# grayhill-knob-board.net
KiCad netlist of a schematic drawn in EAGLE
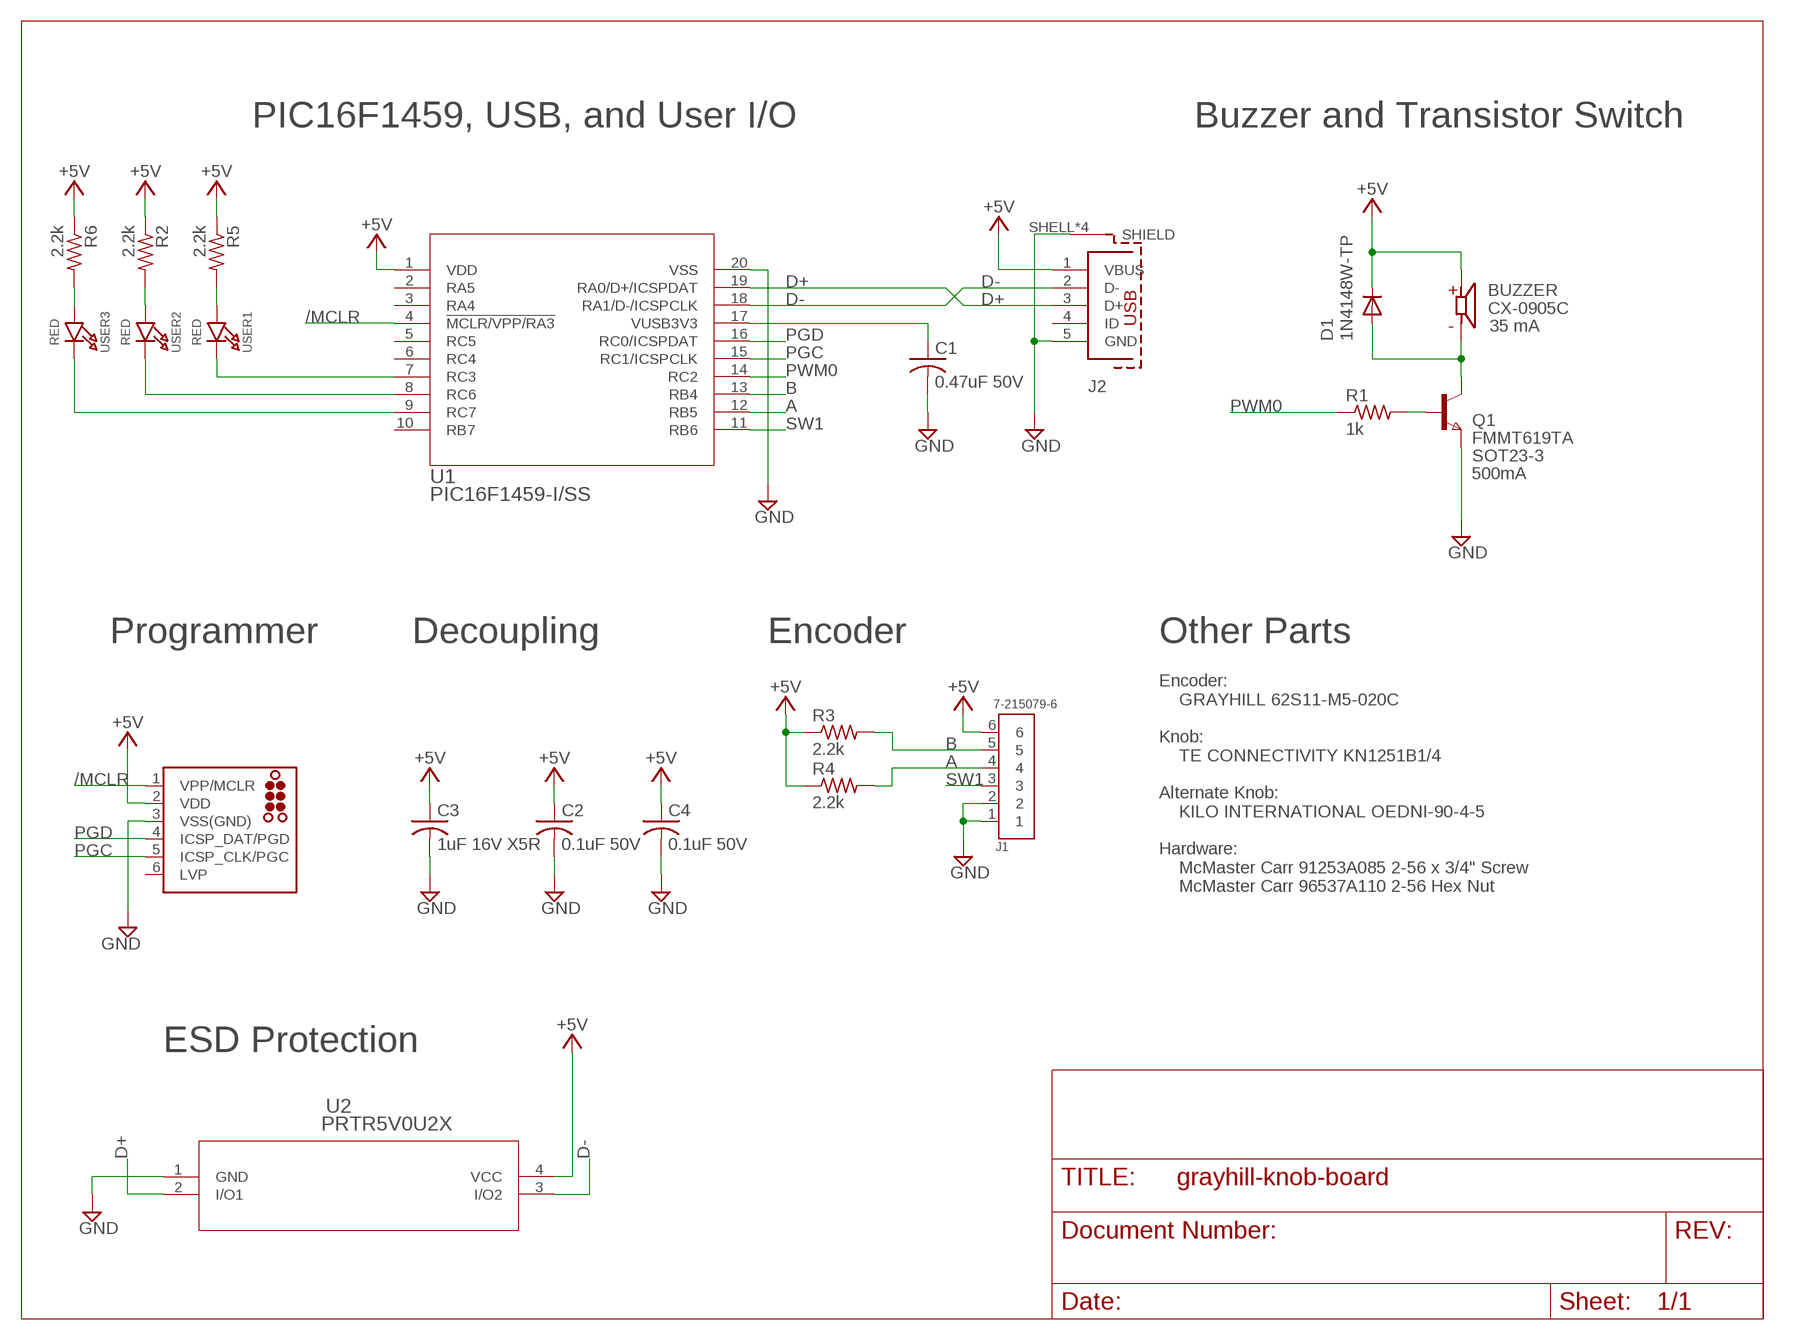
[diagram p0: schematic, sheet 1]

(export (version "E")
  (design (tool "Eeschema 10.0.6"))
  (components
    (comp (ref "BUZZER")
      (value "CX-0905C")
      (footprint "eagle-import:CUI_CX-0905C")
      (fields (field (name "MF") "CUI"))
      (libsource (lib "eagle-import") (part "CX-0905C"))
    )
    (comp (ref "C1")
      (value "0.47uF 50V")
      (footprint "eagle-import:C1206K")
      (fields (field (name "MFR") "KEMET") (field (name "MFR_PART_NO") "C1206C474K5RACTU"))
      (libsource (lib "eagle-import") (part "C-USC1206K"))
    )
    (comp (ref "C2")
      (value "0.1uF 50V")
      (footprint "eagle-import:C1206K")
      (fields (field (name "MFR") "KEMET") (field (name "MFR_PART_NO") "C1206S104M5RACTU"))
      (libsource (lib "eagle-import") (part "C-USC1206K"))
    )
    (comp (ref "C3")
      (value "1uF 16V X5R")
      (footprint "eagle-import:C1210")
      (fields (field (name "MFR") "KEMET") (field (name "MFR_PART_NO") "C1210C105K4PACTU"))
      (libsource (lib "eagle-import") (part "C-USC1210"))
    )
    (comp (ref "C4")
      (value "0.1uF 50V")
      (footprint "eagle-import:C1206K")
      (fields (field (name "MFR") "KEMET") (field (name "MFR_PART_NO") "C1206S104M5RACTU"))
      (libsource (lib "eagle-import") (part "C-USC1206K"))
    )
    (comp (ref "D1")
      (value "1N4148W-TP")
      (footprint "eagle-import:SOD123")
      (libsource (lib "eagle-import") (part "DIODE-SOD123"))
    )
    (comp (ref "J1")
      (value "7-215079-6")
      (footprint "eagle-import:TE_7-215079-6")
      (fields (field (name "DIGI-KEY_PART_NUMBER") "A30729CT-ND") (field (name "MF") "TE Connectivity"))
      (libsource (lib "eagle-import") (part "7-215079-6"))
    )
    (comp (ref "J2")
      (value "629105136821")
      (footprint "eagle-import:629105136821")
      (libsource (lib "eagle-import") (part "629105136821"))
    )
    (comp (ref "J3")
      (value "TC2030-MCP-NL")
      (footprint "eagle-import:TC2030-MCP-NL")
      (libsource (lib "eagle-import") (part "TC2030-MCP-NL"))
    )
    (comp (ref "Q1")
      (value "FMMT619TA")
      (footprint "eagle-import:SOT-23")
      (fields (field (name "MPN") "DSS20201L-7"))
      (libsource (lib "eagle-import") (part "NPNSOT23"))
    )
    (comp (ref "R1")
      (value "1k")
      (footprint "eagle-import:R0805")
      (libsource (lib "eagle-import") (part "R-US_R0805"))
    )
    (comp (ref "R2")
      (value "2.2k")
      (footprint "eagle-import:R0805")
      (libsource (lib "eagle-import") (part "R-US_R0805"))
    )
    (comp (ref "R3")
      (value "2.2k")
      (footprint "eagle-import:R0805")
      (libsource (lib "eagle-import") (part "R-US_R0805"))
    )
    (comp (ref "R4")
      (value "2.2k")
      (footprint "eagle-import:R0805")
      (libsource (lib "eagle-import") (part "R-US_R0805"))
    )
    (comp (ref "R5")
      (value "2.2k")
      (footprint "eagle-import:R0805")
      (libsource (lib "eagle-import") (part "R-US_R0805"))
    )
    (comp (ref "R6")
      (value "2.2k")
      (footprint "eagle-import:R0805")
      (libsource (lib "eagle-import") (part "R-US_R0805"))
    )
    (comp (ref "U1")
      (value "PIC16F1459-I/SS")
      (footprint "eagle-import:SSOP20_MC")
      (fields (field (name "MANUFACTURER_PART_NUMBER") "PIC16F1459ISS"))
      (libsource (lib "eagle-import") (part "PIC16F1459-I/SS"))
    )
    (comp (ref "U2")
      (value "PRTR5V0U2X")
      (footprint "eagle-import:SOT143B")
      (libsource (lib "eagle-import") (part "PRTR5V0U2X"))
    )
    (comp (ref "USER1")
      (value "RED")
      (footprint "eagle-import:CHIPLED_0805_NOOUTLINE")
      (libsource (lib "eagle-import") (part "LED0805_NOOUTLINE"))
    )
    (comp (ref "USER2")
      (value "RED")
      (footprint "eagle-import:CHIPLED_0805_NOOUTLINE")
      (libsource (lib "eagle-import") (part "LED0805_NOOUTLINE"))
    )
    (comp (ref "USER3")
      (value "RED")
      (footprint "eagle-import:CHIPLED_0805_NOOUTLINE")
      (libsource (lib "eagle-import") (part "LED0805_NOOUTLINE"))
    )
  )
  (nets
    (net (code "1") (name "+5V") (class "Default")
      (node (ref "BUZZER") (pin "P") (pinfunction "P_P") (pintype "passive"))
      (node (ref "C2") (pin "1") (pinfunction "1_1") (pintype "passive"))
      (node (ref "C3") (pin "1") (pinfunction "1_1") (pintype "passive"))
      (node (ref "C4") (pin "1") (pinfunction "1_1") (pintype "passive"))
      (node (ref "D1") (pin "C") (pinfunction "C_C") (pintype "passive"))
      (node (ref "J1") (pin "6") (pinfunction "6_6") (pintype "passive"))
      (node (ref "J2") (pin "1") (pinfunction "VBUS_1") (pintype "passive"))
      (node (ref "J3") (pin "2") (pinfunction "VDD_2") (pintype "power_in"))
      (node (ref "R2") (pin "1") (pinfunction "1_1") (pintype "passive"))
      (node (ref "R3") (pin "1") (pinfunction "1_1") (pintype "passive"))
      (node (ref "R4") (pin "1") (pinfunction "1_1") (pintype "passive"))
      (node (ref "R5") (pin "1") (pinfunction "1_1") (pintype "passive"))
      (node (ref "R6") (pin "1") (pinfunction "1_1") (pintype "passive"))
      (node (ref "U1") (pin "1") (pinfunction "VDD_1") (pintype "power_in"))
      (node (ref "U2") (pin "4") (pinfunction "VCC_4") (pintype "passive"))
    )
    (net (code "2") (name "/A") (class "Default")
      (node (ref "J1") (pin "4") (pinfunction "4_4") (pintype "passive"))
      (node (ref "R4") (pin "2") (pinfunction "2_2") (pintype "passive"))
      (node (ref "U1") (pin "12") (pinfunction "RB5_12") (pintype "bidirectional"))
    )
    (net (code "3") (name "/B") (class "Default")
      (node (ref "J1") (pin "5") (pinfunction "5_5") (pintype "passive"))
      (node (ref "R3") (pin "2") (pinfunction "2_2") (pintype "passive"))
      (node (ref "U1") (pin "13") (pinfunction "RB4_13") (pintype "bidirectional"))
    )
    (net (code "4") (name "/D+") (class "Default")
      (node (ref "J2") (pin "3") (pinfunction "D+_3") (pintype "passive"))
      (node (ref "U1") (pin "19") (pinfunction "RA0/D+/ICSPDAT_19") (pintype "bidirectional"))
      (node (ref "U2") (pin "2") (pinfunction "I/O1_2") (pintype "passive"))
    )
    (net (code "5") (name "/D-") (class "Default")
      (node (ref "J2") (pin "2") (pinfunction "D-_2") (pintype "passive"))
      (node (ref "U1") (pin "18") (pinfunction "RA1/D-/ICSPCLK_18") (pintype "bidirectional"))
      (node (ref "U2") (pin "3") (pinfunction "I/O2_3") (pintype "passive"))
    )
    (net (code "6") (name "/PGC") (class "Default")
      (node (ref "J3") (pin "5") (pinfunction "ICSP_CLK/PGC_5") (pintype "output"))
      (node (ref "U1") (pin "15") (pinfunction "RC1/ICSPCLK_15") (pintype "bidirectional"))
    )
    (net (code "7") (name "/PGD") (class "Default")
      (node (ref "J3") (pin "4") (pinfunction "ICSP_DAT/PGD_4") (pintype "bidirectional"))
      (node (ref "U1") (pin "16") (pinfunction "RC0/ICSPDAT_16") (pintype "bidirectional"))
    )
    (net (code "8") (name "/PWM0") (class "Default")
      (node (ref "R1") (pin "1") (pinfunction "1_1") (pintype "passive"))
      (node (ref "U1") (pin "14") (pinfunction "RC2_14") (pintype "bidirectional"))
    )
    (net (code "9") (name "/SW1") (class "Default")
      (node (ref "J1") (pin "3") (pinfunction "3_3") (pintype "passive"))
      (node (ref "U1") (pin "11") (pinfunction "RB6_11") (pintype "bidirectional"))
    )
    (net (code "10") (name "/{slash}MCLR") (class "Default")
      (node (ref "J3") (pin "1") (pinfunction "VPP/MCLR_1") (pintype "passive"))
      (node (ref "U1") (pin "4") (pinfunction "~{MCLR/VPP/RA3}_4") (pintype "bidirectional"))
    )
    (net (code "11") (name "GND") (class "Default")
      (node (ref "C1") (pin "2") (pinfunction "2_2") (pintype "passive"))
      (node (ref "C2") (pin "2") (pinfunction "2_2") (pintype "passive"))
      (node (ref "C3") (pin "2") (pinfunction "2_2") (pintype "passive"))
      (node (ref "C4") (pin "2") (pinfunction "2_2") (pintype "passive"))
      (node (ref "J1") (pin "1") (pinfunction "1_1") (pintype "passive"))
      (node (ref "J1") (pin "2") (pinfunction "2_2") (pintype "passive"))
      (node (ref "J2") (pin "5") (pinfunction "GND_5") (pintype "passive"))
      (node (ref "J2") (pin "SHELL") (pinfunction "SHIELD_SHELL") (pintype "passive"))
      (node (ref "J2") (pin "SHELL1") (pinfunction "SHIELD_SHELL1") (pintype "passive"))
      (node (ref "J2") (pin "SHELL2") (pinfunction "SHIELD_SHELL2") (pintype "passive"))
      (node (ref "J2") (pin "SHELL3") (pinfunction "SHIELD_SHELL3") (pintype "passive"))
      (node (ref "J3") (pin "3") (pinfunction "VSS(GND)_3") (pintype "power_in"))
      (node (ref "Q1") (pin "2") (pinfunction "E_2") (pintype "passive"))
      (node (ref "U1") (pin "20") (pinfunction "VSS_20") (pintype "power_in"))
      (node (ref "U2") (pin "1") (pinfunction "GND_1") (pintype "passive"))
    )
    (net (code "12") (name "Net-(Q1-B)") (class "Default")
      (node (ref "Q1") (pin "3") (pinfunction "B_3") (pintype "passive"))
      (node (ref "R1") (pin "2") (pinfunction "2_2") (pintype "passive"))
    )
    (net (code "13") (name "Net-(Q1-C)") (class "Default")
      (node (ref "BUZZER") (pin "N") (pinfunction "N_N") (pintype "passive"))
      (node (ref "D1") (pin "A") (pinfunction "A_A") (pintype "passive"))
      (node (ref "Q1") (pin "1") (pinfunction "C_1") (pintype "passive"))
    )
    (net (code "14") (name "Net-(R2-Pad2)") (class "Default")
      (node (ref "R2") (pin "2") (pinfunction "2_2") (pintype "passive"))
      (node (ref "USER2") (pin "A") (pinfunction "A_A") (pintype "passive"))
    )
    (net (code "15") (name "Net-(R5-Pad2)") (class "Default")
      (node (ref "R5") (pin "2") (pinfunction "2_2") (pintype "passive"))
      (node (ref "USER1") (pin "A") (pinfunction "A_A") (pintype "passive"))
    )
    (net (code "16") (name "Net-(R6-Pad2)") (class "Default")
      (node (ref "R6") (pin "2") (pinfunction "2_2") (pintype "passive"))
      (node (ref "USER3") (pin "A") (pinfunction "A_A") (pintype "passive"))
    )
    (net (code "17") (name "Net-(U1-RC3)") (class "Default")
      (node (ref "U1") (pin "7") (pinfunction "RC3_7") (pintype "bidirectional"))
      (node (ref "USER1") (pin "C") (pinfunction "C_C") (pintype "passive"))
    )
    (net (code "18") (name "Net-(U1-RC6)") (class "Default")
      (node (ref "U1") (pin "8") (pinfunction "RC6_8") (pintype "bidirectional"))
      (node (ref "USER2") (pin "C") (pinfunction "C_C") (pintype "passive"))
    )
    (net (code "19") (name "Net-(U1-RC7)") (class "Default")
      (node (ref "U1") (pin "9") (pinfunction "RC7_9") (pintype "bidirectional"))
      (node (ref "USER3") (pin "C") (pinfunction "C_C") (pintype "passive"))
    )
    (net (code "20") (name "Net-(U1-VUSB3V3)") (class "Default")
      (node (ref "C1") (pin "1") (pinfunction "1_1") (pintype "passive"))
      (node (ref "U1") (pin "17") (pinfunction "VUSB3V3_17") (pintype "power_in"))
    )
    (net (code "21") (name "unconnected-(J2-ID-Pad4)") (class "Default")
      (node (ref "J2") (pin "4") (pinfunction "ID_4") (pintype "passive"))
    )
    (net (code "22") (name "unconnected-(J3-LVP-Pad6)") (class "Default")
      (node (ref "J3") (pin "6") (pinfunction "LVP_6") (pintype "bidirectional"))
    )
    (net (code "23") (name "unconnected-(U1-RA4-Pad3)") (class "Default")
      (node (ref "U1") (pin "3") (pinfunction "RA4_3") (pintype "bidirectional"))
    )
    (net (code "24") (name "unconnected-(U1-RA5-Pad2)") (class "Default")
      (node (ref "U1") (pin "2") (pinfunction "RA5_2") (pintype "bidirectional"))
    )
    (net (code "25") (name "unconnected-(U1-RB7-Pad10)") (class "Default")
      (node (ref "U1") (pin "10") (pinfunction "RB7_10") (pintype "bidirectional"))
    )
    (net (code "26") (name "unconnected-(U1-RC4-Pad6)") (class "Default")
      (node (ref "U1") (pin "6") (pinfunction "RC4_6") (pintype "bidirectional"))
    )
    (net (code "27") (name "unconnected-(U1-RC5-Pad5)") (class "Default")
      (node (ref "U1") (pin "5") (pinfunction "RC5_5") (pintype "bidirectional"))
    )
  )
)
